# 5V-12Visolated.net
KiCad netlist of a schematic drawn in Altium Designer
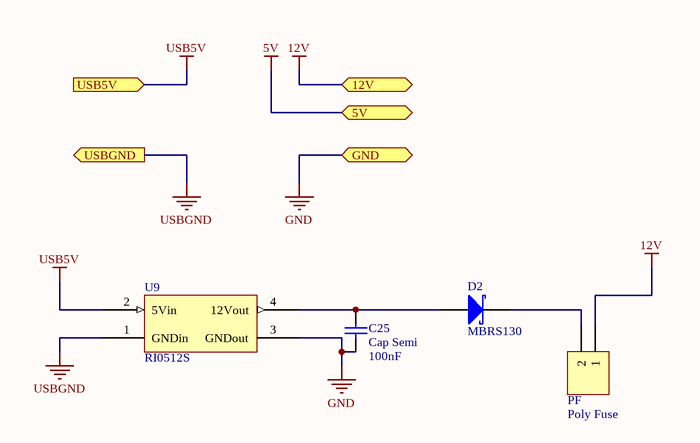
[diagram p0: 5V-12Visolated.SchDoc]

(export (version "E")
  (design (tool "Eeschema 10.0.6"))
  (components
    (comp (ref "C25")
      (value "Cap Semi")
      (footprint "0603")
      (description "Capacitor (Semiconductor SIM Model)")
      (fields (field (name "ALTIUM_VALUE") "100nF") (field (name "PUBLISHER") "Altium Limited"))
      (libsource (lib "Miscellaneous Devices") (part "Cap Semi"))
    )
    (comp (ref "D2")
      (value "MBRS130")
      (footprint "SMB")
      (description "Schottky Diode")
      (libsource (lib "RCLDQ") (part "D SCHOTTKY"))
    )
    (comp (ref "PF")
      (value "Poly Fuse")
      (footprint "HDR1X2")
      (description "Header, 2-Pin")
      (fields (field (name "PUBLISHER") "Altium Limited"))
      (libsource (lib "Miscellaneous Connectors") (part "Header 2"))
    )
    (comp (ref "U9")
      (value "RI0512S")
      (footprint "DIP8")
      (description "5V-12V isolated")
      (libsource (lib "DCDC-Converters") (part "RI0512S"))
    )
  )
  (nets
    (net (code "2") (name "12V") (class "Default")
      (node (ref "PF") (pin "1") (pinfunction "1_1") (pintype "passive"))
    )
    (net (code "3") (name "GND") (class "Default")
      (node (ref "C25") (pin "2") (pinfunction "2_2") (pintype "passive"))
      (node (ref "U9") (pin "3") (pinfunction "GNDout_3") (pintype "passive"))
    )
    (net (code "4") (name "Net-(D2-PadK)") (class "Default")
      (node (ref "D2") (pin "K") (pinfunction "K_K") (pintype "passive"))
      (node (ref "PF") (pin "2") (pinfunction "2_2") (pintype "passive"))
    )
    (net (code "5") (name "Net-(U9-12Vout)") (class "Default")
      (node (ref "C25") (pin "1") (pinfunction "1_1") (pintype "passive"))
      (node (ref "D2") (pin "A") (pinfunction "A_A") (pintype "passive"))
      (node (ref "U9") (pin "4") (pinfunction "12Vout_4") (pintype "output"))
    )
    (net (code "6") (name "USB5V") (class "Default")
      (node (ref "U9") (pin "2") (pinfunction "5Vin_2") (pintype "input"))
    )
    (net (code "7") (name "USBGND") (class "Default")
      (node (ref "U9") (pin "1") (pinfunction "GNDin_1") (pintype "passive"))
    )
  )
)
